# adg731-switches.net
KiCad netlist of a schematic drawn in Altium Designer
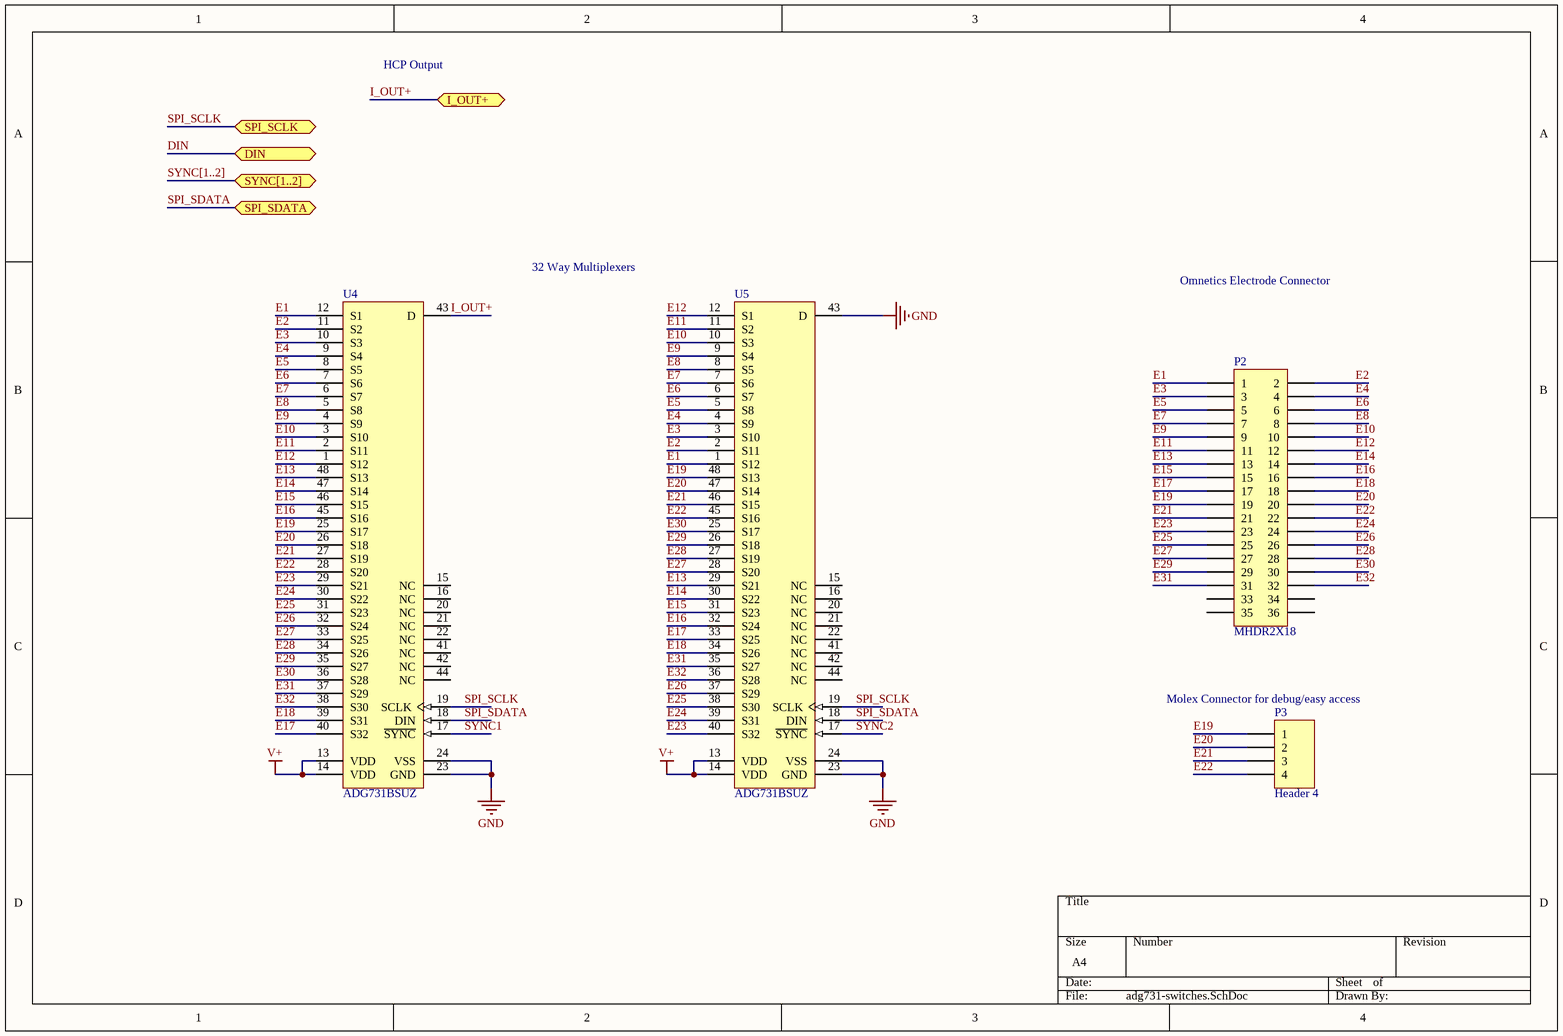
[diagram p0: adg731-switches.SchDoc]

(export (version "E")
  (design (tool "Eeschema 10.0.6"))
  (components
    (comp (ref "P2")
      (value "MHDR2X18")
      (footprint "A79025-001")
      (description "Header, 18-Pin, Dual row")
      (fields (field (name "PUBLISHER") "Altium Limited"))
      (libsource (lib "Miscellaneous Connectors") (part "MHDR2X18"))
    )
    (comp (ref "P3")
      (value "Header 4")
      (footprint "HDR1X4")
      (description "Header, 4-Pin")
      (fields (field (name "PUBLISHER") "Altium Limited"))
      (libsource (lib "Miscellaneous Connectors") (part "Header 4"))
    )
    (comp (ref "U4")
      (value "ADG731BSUZ")
      (footprint "ADI-SU-48_N")
      (fields (field (name "MANUFACTURER") "Analog Devices"))
      (libsource (lib "Altium Content Vault") (part "CMP-0798-00240-1"))
    )
    (comp (ref "U5")
      (value "ADG731BSUZ")
      (footprint "ADI-SU-48_N")
      (fields (field (name "MANUFACTURER") "Analog Devices"))
      (libsource (lib "Altium Content Vault") (part "CMP-0798-00240-1"))
    )
  )
  (nets
    (net (code "2") (name "/E1") (class "Default")
      (node (ref "P2") (pin "1") (pinfunction "1_1") (pintype "passive"))
      (node (ref "U4") (pin "12") (pinfunction "S1_12") (pintype "passive"))
      (node (ref "U5") (pin "1") (pinfunction "S12_1") (pintype "passive"))
    )
    (net (code "3") (name "/E2") (class "Default")
      (node (ref "P2") (pin "2") (pinfunction "2_2") (pintype "passive"))
      (node (ref "U4") (pin "11") (pinfunction "S2_11") (pintype "passive"))
      (node (ref "U5") (pin "2") (pinfunction "S11_2") (pintype "passive"))
    )
    (net (code "4") (name "/E3") (class "Default")
      (node (ref "P2") (pin "3") (pinfunction "3_3") (pintype "passive"))
      (node (ref "U4") (pin "10") (pinfunction "S3_10") (pintype "passive"))
      (node (ref "U5") (pin "3") (pinfunction "S10_3") (pintype "passive"))
    )
    (net (code "5") (name "/E4") (class "Default")
      (node (ref "P2") (pin "4") (pinfunction "4_4") (pintype "passive"))
      (node (ref "U4") (pin "9") (pinfunction "S4_9") (pintype "passive"))
      (node (ref "U5") (pin "4") (pinfunction "S9_4") (pintype "passive"))
    )
    (net (code "6") (name "/E5") (class "Default")
      (node (ref "P2") (pin "5") (pinfunction "5_5") (pintype "passive"))
      (node (ref "U4") (pin "8") (pinfunction "S5_8") (pintype "passive"))
      (node (ref "U5") (pin "5") (pinfunction "S8_5") (pintype "passive"))
    )
    (net (code "7") (name "/E6") (class "Default")
      (node (ref "P2") (pin "6") (pinfunction "6_6") (pintype "passive"))
      (node (ref "U4") (pin "7") (pinfunction "S6_7") (pintype "passive"))
      (node (ref "U5") (pin "6") (pinfunction "S7_6") (pintype "passive"))
    )
    (net (code "8") (name "/E7") (class "Default")
      (node (ref "P2") (pin "7") (pinfunction "7_7") (pintype "passive"))
      (node (ref "U4") (pin "6") (pinfunction "S7_6") (pintype "passive"))
      (node (ref "U5") (pin "7") (pinfunction "S6_7") (pintype "passive"))
    )
    (net (code "9") (name "/E8") (class "Default")
      (node (ref "P2") (pin "8") (pinfunction "8_8") (pintype "passive"))
      (node (ref "U4") (pin "5") (pinfunction "S8_5") (pintype "passive"))
      (node (ref "U5") (pin "8") (pinfunction "S5_8") (pintype "passive"))
    )
    (net (code "10") (name "/E9") (class "Default")
      (node (ref "P2") (pin "9") (pinfunction "9_9") (pintype "passive"))
      (node (ref "U4") (pin "4") (pinfunction "S9_4") (pintype "passive"))
      (node (ref "U5") (pin "9") (pinfunction "S4_9") (pintype "passive"))
    )
    (net (code "11") (name "/E10") (class "Default")
      (node (ref "P2") (pin "10") (pinfunction "10_10") (pintype "passive"))
      (node (ref "U4") (pin "3") (pinfunction "S10_3") (pintype "passive"))
      (node (ref "U5") (pin "10") (pinfunction "S3_10") (pintype "passive"))
    )
    (net (code "12") (name "/E11") (class "Default")
      (node (ref "P2") (pin "11") (pinfunction "11_11") (pintype "passive"))
      (node (ref "U4") (pin "2") (pinfunction "S11_2") (pintype "passive"))
      (node (ref "U5") (pin "11") (pinfunction "S2_11") (pintype "passive"))
    )
    (net (code "13") (name "/E12") (class "Default")
      (node (ref "P2") (pin "12") (pinfunction "12_12") (pintype "passive"))
      (node (ref "U4") (pin "1") (pinfunction "S12_1") (pintype "passive"))
      (node (ref "U5") (pin "12") (pinfunction "S1_12") (pintype "passive"))
    )
    (net (code "14") (name "/E13") (class "Default")
      (node (ref "P2") (pin "13") (pinfunction "13_13") (pintype "passive"))
      (node (ref "U4") (pin "48") (pinfunction "S13_48") (pintype "passive"))
      (node (ref "U5") (pin "29") (pinfunction "S21_29") (pintype "passive"))
    )
    (net (code "15") (name "/E14") (class "Default")
      (node (ref "P2") (pin "14") (pinfunction "14_14") (pintype "passive"))
      (node (ref "U4") (pin "47") (pinfunction "S14_47") (pintype "passive"))
      (node (ref "U5") (pin "30") (pinfunction "S22_30") (pintype "passive"))
    )
    (net (code "16") (name "/E15") (class "Default")
      (node (ref "P2") (pin "15") (pinfunction "15_15") (pintype "passive"))
      (node (ref "U4") (pin "46") (pinfunction "S15_46") (pintype "passive"))
      (node (ref "U5") (pin "31") (pinfunction "S23_31") (pintype "passive"))
    )
    (net (code "17") (name "/E16") (class "Default")
      (node (ref "P2") (pin "16") (pinfunction "16_16") (pintype "passive"))
      (node (ref "U4") (pin "45") (pinfunction "S16_45") (pintype "passive"))
      (node (ref "U5") (pin "32") (pinfunction "S24_32") (pintype "passive"))
    )
    (net (code "18") (name "/E17") (class "Default")
      (node (ref "P2") (pin "17") (pinfunction "17_17") (pintype "passive"))
      (node (ref "U4") (pin "40") (pinfunction "S32_40") (pintype "passive"))
      (node (ref "U5") (pin "33") (pinfunction "S25_33") (pintype "passive"))
    )
    (net (code "19") (name "/E18") (class "Default")
      (node (ref "P2") (pin "18") (pinfunction "18_18") (pintype "passive"))
      (node (ref "U4") (pin "39") (pinfunction "S31_39") (pintype "passive"))
      (node (ref "U5") (pin "34") (pinfunction "S26_34") (pintype "passive"))
    )
    (net (code "20") (name "/E19") (class "Default")
      (node (ref "P2") (pin "19") (pinfunction "19_19") (pintype "passive"))
      (node (ref "P3") (pin "1") (pinfunction "1_1") (pintype "passive"))
      (node (ref "U4") (pin "25") (pinfunction "S17_25") (pintype "passive"))
      (node (ref "U5") (pin "48") (pinfunction "S13_48") (pintype "passive"))
    )
    (net (code "21") (name "/E20") (class "Default")
      (node (ref "P2") (pin "20") (pinfunction "20_20") (pintype "passive"))
      (node (ref "P3") (pin "2") (pinfunction "2_2") (pintype "passive"))
      (node (ref "U4") (pin "26") (pinfunction "S18_26") (pintype "passive"))
      (node (ref "U5") (pin "47") (pinfunction "S14_47") (pintype "passive"))
    )
    (net (code "22") (name "/E21") (class "Default")
      (node (ref "P2") (pin "21") (pinfunction "21_21") (pintype "passive"))
      (node (ref "P3") (pin "3") (pinfunction "3_3") (pintype "passive"))
      (node (ref "U4") (pin "27") (pinfunction "S19_27") (pintype "passive"))
      (node (ref "U5") (pin "46") (pinfunction "S15_46") (pintype "passive"))
    )
    (net (code "23") (name "/E22") (class "Default")
      (node (ref "P2") (pin "22") (pinfunction "22_22") (pintype "passive"))
      (node (ref "P3") (pin "4") (pinfunction "4_4") (pintype "passive"))
      (node (ref "U4") (pin "28") (pinfunction "S20_28") (pintype "passive"))
      (node (ref "U5") (pin "45") (pinfunction "S16_45") (pintype "passive"))
    )
    (net (code "24") (name "/E23") (class "Default")
      (node (ref "P2") (pin "23") (pinfunction "23_23") (pintype "passive"))
      (node (ref "U4") (pin "29") (pinfunction "S21_29") (pintype "passive"))
      (node (ref "U5") (pin "40") (pinfunction "S32_40") (pintype "passive"))
    )
    (net (code "25") (name "/E24") (class "Default")
      (node (ref "P2") (pin "24") (pinfunction "24_24") (pintype "passive"))
      (node (ref "U4") (pin "30") (pinfunction "S22_30") (pintype "passive"))
      (node (ref "U5") (pin "39") (pinfunction "S31_39") (pintype "passive"))
    )
    (net (code "26") (name "/E25") (class "Default")
      (node (ref "P2") (pin "25") (pinfunction "25_25") (pintype "passive"))
      (node (ref "U4") (pin "31") (pinfunction "S23_31") (pintype "passive"))
      (node (ref "U5") (pin "38") (pinfunction "S30_38") (pintype "passive"))
    )
    (net (code "27") (name "/E26") (class "Default")
      (node (ref "P2") (pin "26") (pinfunction "26_26") (pintype "passive"))
      (node (ref "U4") (pin "32") (pinfunction "S24_32") (pintype "passive"))
      (node (ref "U5") (pin "37") (pinfunction "S29_37") (pintype "passive"))
    )
    (net (code "28") (name "/E27") (class "Default")
      (node (ref "P2") (pin "27") (pinfunction "27_27") (pintype "passive"))
      (node (ref "U4") (pin "33") (pinfunction "S25_33") (pintype "passive"))
      (node (ref "U5") (pin "28") (pinfunction "S20_28") (pintype "passive"))
    )
    (net (code "29") (name "/E28") (class "Default")
      (node (ref "P2") (pin "28") (pinfunction "28_28") (pintype "passive"))
      (node (ref "U4") (pin "34") (pinfunction "S26_34") (pintype "passive"))
      (node (ref "U5") (pin "27") (pinfunction "S19_27") (pintype "passive"))
    )
    (net (code "30") (name "/E29") (class "Default")
      (node (ref "P2") (pin "29") (pinfunction "29_29") (pintype "passive"))
      (node (ref "U4") (pin "35") (pinfunction "S27_35") (pintype "passive"))
      (node (ref "U5") (pin "26") (pinfunction "S18_26") (pintype "passive"))
    )
    (net (code "31") (name "/E30") (class "Default")
      (node (ref "P2") (pin "30") (pinfunction "30_30") (pintype "passive"))
      (node (ref "U4") (pin "36") (pinfunction "S28_36") (pintype "passive"))
      (node (ref "U5") (pin "25") (pinfunction "S17_25") (pintype "passive"))
    )
    (net (code "32") (name "/E31") (class "Default")
      (node (ref "P2") (pin "31") (pinfunction "31_31") (pintype "passive"))
      (node (ref "U4") (pin "37") (pinfunction "S29_37") (pintype "passive"))
      (node (ref "U5") (pin "35") (pinfunction "S27_35") (pintype "passive"))
    )
    (net (code "33") (name "/E32") (class "Default")
      (node (ref "P2") (pin "32") (pinfunction "32_32") (pintype "passive"))
      (node (ref "U4") (pin "38") (pinfunction "S30_38") (pintype "passive"))
      (node (ref "U5") (pin "36") (pinfunction "S28_36") (pintype "passive"))
    )
    (net (code "34") (name "/I_OUT+") (class "Default")
      (node (ref "U4") (pin "43") (pinfunction "D_43") (pintype "passive"))
    )
    (net (code "35") (name "/SPI_SCLK") (class "Default")
      (node (ref "U4") (pin "19") (pinfunction "SCLK_19") (pintype "input"))
      (node (ref "U5") (pin "19") (pinfunction "SCLK_19") (pintype "input"))
    )
    (net (code "36") (name "/SPI_SDATA") (class "Default")
      (node (ref "U4") (pin "18") (pinfunction "DIN_18") (pintype "input"))
      (node (ref "U5") (pin "18") (pinfunction "DIN_18") (pintype "input"))
    )
    (net (code "37") (name "/SYNC1") (class "Default")
      (node (ref "U4") (pin "17") (pinfunction "~{SYNC}_17") (pintype "input"))
    )
    (net (code "38") (name "/SYNC2") (class "Default")
      (node (ref "U5") (pin "17") (pinfunction "~{SYNC}_17") (pintype "input"))
    )
    (net (code "40") (name "GND") (class "Default")
      (node (ref "U4") (pin "23") (pinfunction "GND_23") (pintype "power_in"))
      (node (ref "U4") (pin "24") (pinfunction "VSS_24") (pintype "power_in"))
      (node (ref "U5") (pin "23") (pinfunction "GND_23") (pintype "power_in"))
      (node (ref "U5") (pin "24") (pinfunction "VSS_24") (pintype "power_in"))
      (node (ref "U5") (pin "43") (pinfunction "D_43") (pintype "passive"))
    )
    (net (code "41") (name "V+") (class "Default")
      (node (ref "U4") (pin "13") (pinfunction "VDD_13") (pintype "power_in"))
      (node (ref "U4") (pin "14") (pinfunction "VDD_14") (pintype "power_in"))
      (node (ref "U5") (pin "13") (pinfunction "VDD_13") (pintype "power_in"))
      (node (ref "U5") (pin "14") (pinfunction "VDD_14") (pintype "power_in"))
    )
    (net (code "42") (name "unconnected-(P2-Pad33)") (class "Default")
      (node (ref "P2") (pin "33") (pinfunction "33_33") (pintype "passive"))
    )
    (net (code "43") (name "unconnected-(P2-Pad34)") (class "Default")
      (node (ref "P2") (pin "34") (pinfunction "34_34") (pintype "passive"))
    )
    (net (code "44") (name "unconnected-(P2-Pad35)") (class "Default")
      (node (ref "P2") (pin "35") (pinfunction "35_35") (pintype "passive"))
    )
    (net (code "45") (name "unconnected-(P2-Pad36)") (class "Default")
      (node (ref "P2") (pin "36") (pinfunction "36_36") (pintype "passive"))
    )
    (net (code "46") (name "unconnected-(U4-NC-Pad15)") (class "Default")
      (node (ref "U4") (pin "15") (pinfunction "NC_15") (pintype "passive"))
    )
    (net (code "47") (name "unconnected-(U4-NC-Pad16)") (class "Default")
      (node (ref "U4") (pin "16") (pinfunction "NC_16") (pintype "passive"))
    )
    (net (code "48") (name "unconnected-(U4-NC-Pad20)") (class "Default")
      (node (ref "U4") (pin "20") (pinfunction "NC_20") (pintype "passive"))
    )
    (net (code "49") (name "unconnected-(U4-NC-Pad21)") (class "Default")
      (node (ref "U4") (pin "21") (pinfunction "NC_21") (pintype "passive"))
    )
    (net (code "50") (name "unconnected-(U4-NC-Pad22)") (class "Default")
      (node (ref "U4") (pin "22") (pinfunction "NC_22") (pintype "passive"))
    )
    (net (code "51") (name "unconnected-(U4-NC-Pad41)") (class "Default")
      (node (ref "U4") (pin "41") (pinfunction "NC_41") (pintype "passive"))
    )
    (net (code "52") (name "unconnected-(U4-NC-Pad42)") (class "Default")
      (node (ref "U4") (pin "42") (pinfunction "NC_42") (pintype "passive"))
    )
    (net (code "53") (name "unconnected-(U4-NC-Pad44)") (class "Default")
      (node (ref "U4") (pin "44") (pinfunction "NC_44") (pintype "passive"))
    )
    (net (code "54") (name "unconnected-(U5-NC-Pad15)") (class "Default")
      (node (ref "U5") (pin "15") (pinfunction "NC_15") (pintype "passive"))
    )
    (net (code "55") (name "unconnected-(U5-NC-Pad16)") (class "Default")
      (node (ref "U5") (pin "16") (pinfunction "NC_16") (pintype "passive"))
    )
    (net (code "56") (name "unconnected-(U5-NC-Pad20)") (class "Default")
      (node (ref "U5") (pin "20") (pinfunction "NC_20") (pintype "passive"))
    )
    (net (code "57") (name "unconnected-(U5-NC-Pad21)") (class "Default")
      (node (ref "U5") (pin "21") (pinfunction "NC_21") (pintype "passive"))
    )
    (net (code "58") (name "unconnected-(U5-NC-Pad22)") (class "Default")
      (node (ref "U5") (pin "22") (pinfunction "NC_22") (pintype "passive"))
    )
    (net (code "59") (name "unconnected-(U5-NC-Pad41)") (class "Default")
      (node (ref "U5") (pin "41") (pinfunction "NC_41") (pintype "passive"))
    )
    (net (code "60") (name "unconnected-(U5-NC-Pad42)") (class "Default")
      (node (ref "U5") (pin "42") (pinfunction "NC_42") (pintype "passive"))
    )
    (net (code "61") (name "unconnected-(U5-NC-Pad44)") (class "Default")
      (node (ref "U5") (pin "44") (pinfunction "NC_44") (pintype "passive"))
    )
  )
)
